# Gimbal_Controller_Board.net
KiCad netlist of a schematic drawn in EAGLE
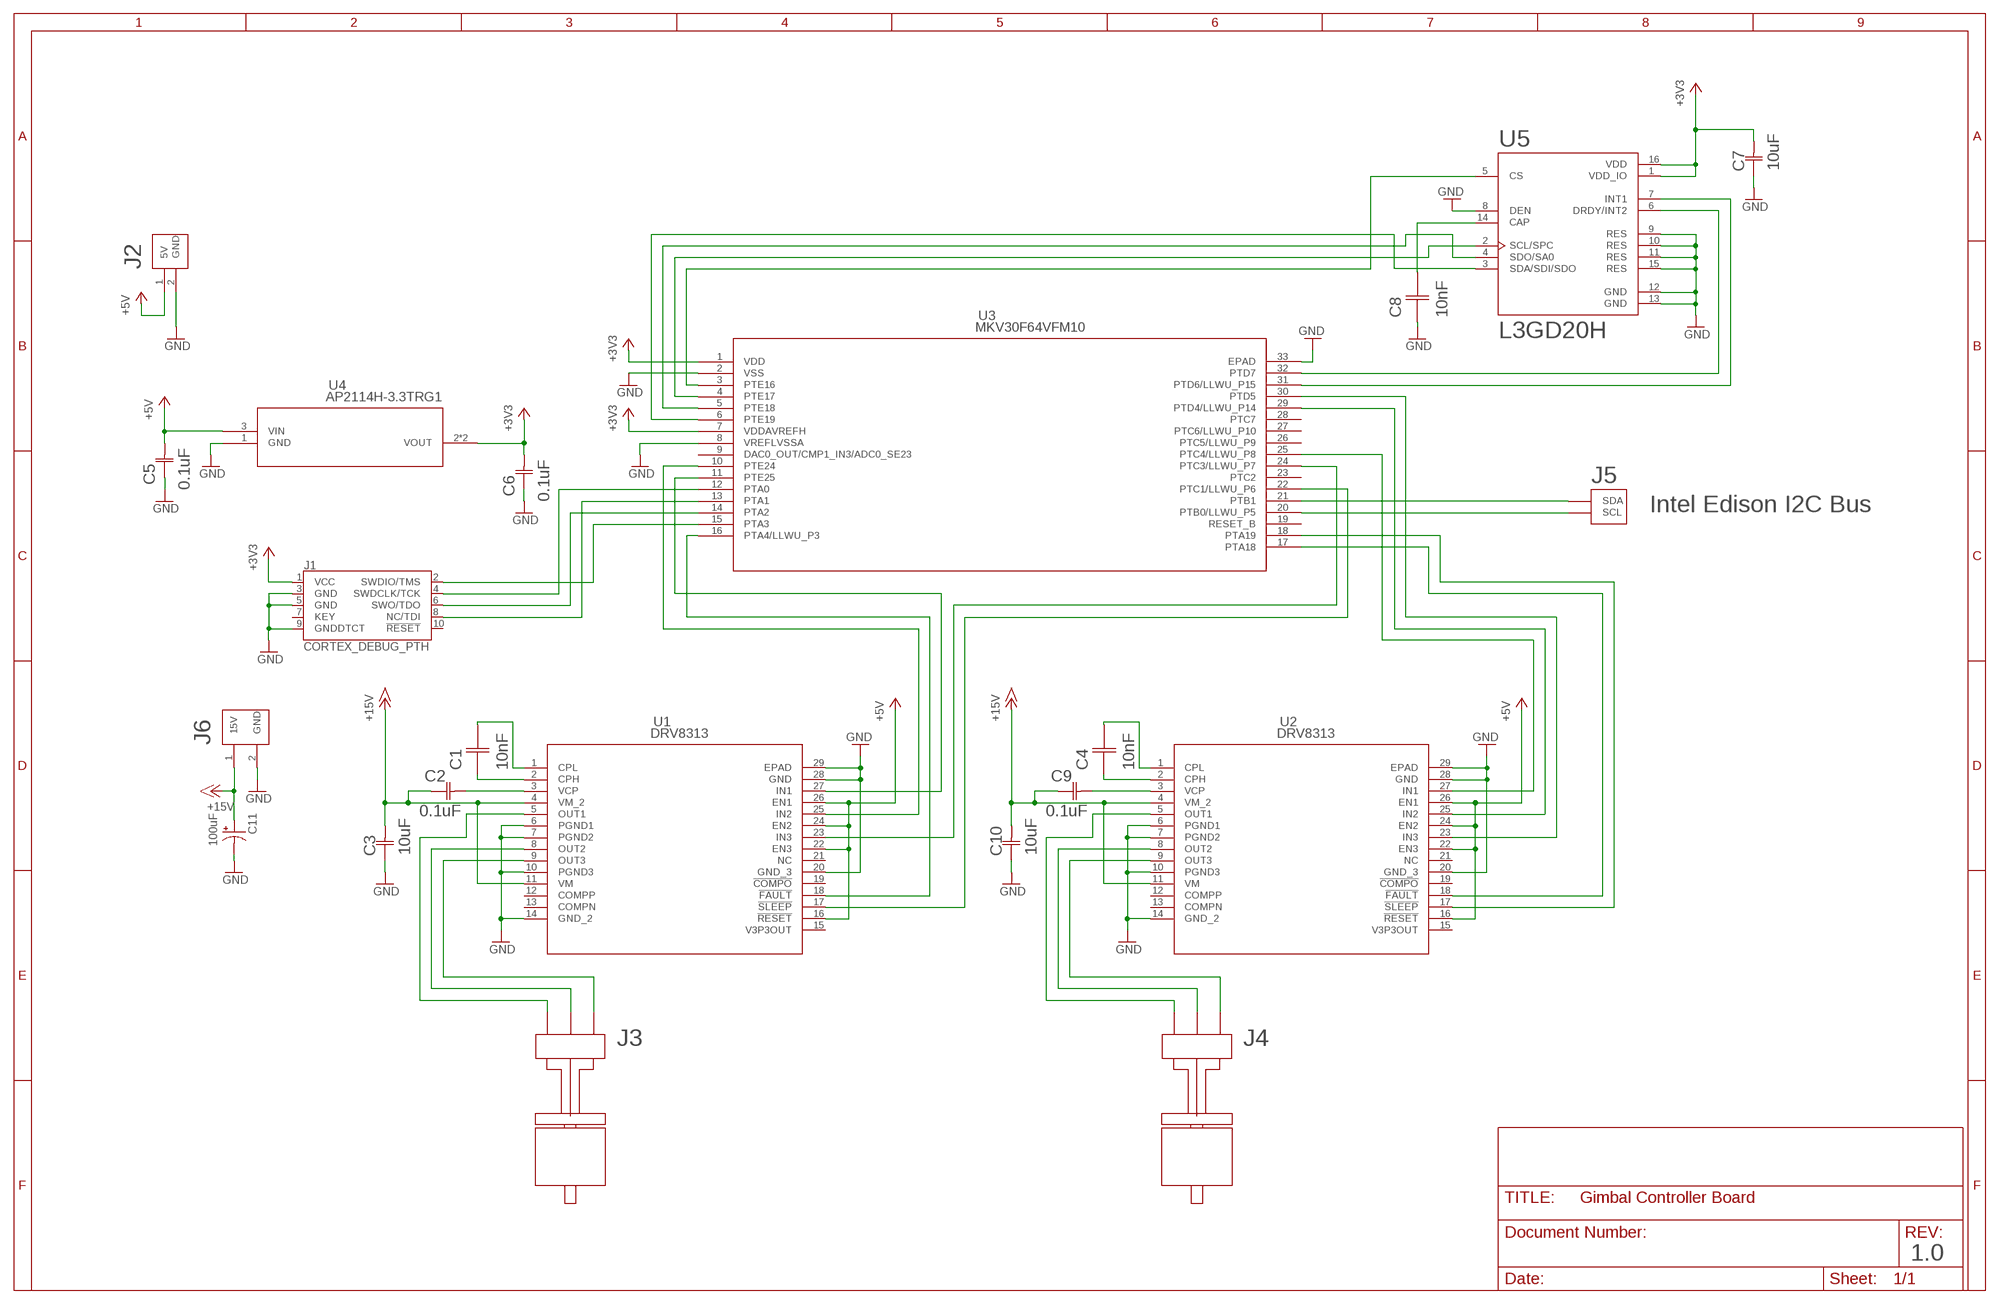
[diagram p0: schematic, sheet 1]

(export (version "E")
  (design (tool "Eeschema 10.0.6"))
  (components
    (comp (ref "C1")
      (value "10nF")
      (footprint "eagle-import:0603_CAPACITOR")
      (libsource (lib "eagle-import") (part "10NF_CAPACITOR"))
    )
    (comp (ref "C2")
      (value "0.1uF")
      (footprint "eagle-import:0805")
      (fields
        (field (name "MANUFACTURER_PART_NUMBER") "08055C104KAT2A")
        (field (name "COPYRIGHT") "Copyright C 2015 Accelerated Designs. All rights reserved")
      )
      (libsource (lib "eagle-import") (part "08055C104KAT2A"))
    )
    (comp (ref "C3")
      (value "10uF")
      (footprint "eagle-import:G-21")
      (fields
        (field (name "MANUFACTURER_PART_NUMBER") "GRM21BR60J106ME19L")
        (field (name "COPYRIGHT") "Copyright C 2015 Accelerated Designs. All rights reserved")
      )
      (libsource (lib "eagle-import") (part "GRM21BR60J106ME19L"))
    )
    (comp (ref "C4")
      (value "10nF")
      (footprint "eagle-import:0603_CAPACITOR")
      (libsource (lib "eagle-import") (part "10NF_CAPACITOR"))
    )
    (comp (ref "C5")
      (value "0.1uF")
      (footprint "eagle-import:0805")
      (fields
        (field (name "MANUFACTURER_PART_NUMBER") "08055C104KAT2A")
        (field (name "COPYRIGHT") "Copyright C 2015 Accelerated Designs. All rights reserved")
      )
      (libsource (lib "eagle-import") (part "08055C104KAT2A"))
    )
    (comp (ref "C6")
      (value "0.1uF")
      (footprint "eagle-import:0805")
      (fields
        (field (name "MANUFACTURER_PART_NUMBER") "08055C104KAT2A")
        (field (name "COPYRIGHT") "Copyright C 2015 Accelerated Designs. All rights reserved")
      )
      (libsource (lib "eagle-import") (part "08055C104KAT2A"))
    )
    (comp (ref "C7")
      (value "10uF")
      (footprint "eagle-import:G-21")
      (fields
        (field (name "MANUFACTURER_PART_NUMBER") "GRM21BR60J106ME19L")
        (field (name "COPYRIGHT") "Copyright C 2015 Accelerated Designs. All rights reserved")
      )
      (libsource (lib "eagle-import") (part "GRM21BR60J106ME19L"))
    )
    (comp (ref "C8")
      (value "10nF")
      (footprint "eagle-import:0603_CAPACITOR")
      (libsource (lib "eagle-import") (part "10NF_CAPACITOR"))
    )
    (comp (ref "C9")
      (value "0.1uF")
      (footprint "eagle-import:0805")
      (fields
        (field (name "MANUFACTURER_PART_NUMBER") "08055C104KAT2A")
        (field (name "COPYRIGHT") "Copyright C 2015 Accelerated Designs. All rights reserved")
      )
      (libsource (lib "eagle-import") (part "08055C104KAT2A"))
    )
    (comp (ref "C10")
      (value "10uF")
      (footprint "eagle-import:G-21")
      (fields
        (field (name "MANUFACTURER_PART_NUMBER") "GRM21BR60J106ME19L")
        (field (name "COPYRIGHT") "Copyright C 2015 Accelerated Designs. All rights reserved")
      )
      (libsource (lib "eagle-import") (part "GRM21BR60J106ME19L"))
    )
    (comp (ref "C11")
      (value "100uF")
      (footprint "eagle-import:0810_POLCAP")
      (libsource (lib "eagle-import") (part "100UF_CAPACITOR"))
    )
    (comp (ref "J1")
      (value "CORTEX_DEBUG_PTH")
      (footprint "eagle-import:2X5-PTH-1.27MM")
      (libsource (lib "eagle-import") (part "CORTEX_DEBUG_PTH"))
    )
    (comp (ref "J2")
      (value "POWER_CONNECTOR")
      (footprint "eagle-import:XH_CONNECTOR")
      (libsource (lib "eagle-import") (part "POWER_CONNECTOR"))
    )
    (comp (ref "J3")
      (value "BLDC_MOTOR_CONNECTOR")
      (footprint "eagle-import:JST-XH_3POS")
      (libsource (lib "eagle-import") (part "BLDC_MOTOR_CONNECTOR"))
    )
    (comp (ref "J4")
      (value "BLDC_MOTOR_CONNECTOR")
      (footprint "eagle-import:JST-XH_3POS")
      (libsource (lib "eagle-import") (part "BLDC_MOTOR_CONNECTOR"))
    )
    (comp (ref "J5")
      (value "I2C_CONNECTOR")
      (footprint "eagle-import:XH_CONNECTOR")
      (libsource (lib "eagle-import") (part "I2C_CONNECTOR"))
    )
    (comp (ref "J6")
      (value "GIMBAL_POWER_CONNECTOR")
      (footprint "eagle-import:XH_CONNECTOR")
      (libsource (lib "eagle-import") (part "GIMBAL_POWER_CONNECTOR"))
    )
    (comp (ref "U1")
      (value "DRV8313")
      (footprint "eagle-import:PWP28_5P18X3P1-M")
      (fields (field (name "MANUFACTURER_PART_NUMBER") "drv8313pwp"))
      (libsource (lib "eagle-import") (part "DRV8313PWPRPWP28_5P18X3P1-M"))
    )
    (comp (ref "U2")
      (value "DRV8313")
      (footprint "eagle-import:PWP28_5P18X3P1-M")
      (fields (field (name "MANUFACTURER_PART_NUMBER") "drv8313pwp"))
      (libsource (lib "eagle-import") (part "DRV8313PWPRPWP28_5P18X3P1-M"))
    )
    (comp (ref "U3")
      (value "MKV30F64VFM10")
      (footprint "eagle-import:QFN-32_5X5X0.9")
      (fields (field (name "MANUFACTURER_PART_NUMBER") "mkv30f64vfm10"))
      (libsource (lib "eagle-import") (part "MKV30F64VFM10"))
    )
    (comp (ref "U4")
      (value "AP2114H-3.3TRG1")
      (footprint "eagle-import:SOT-223")
      (fields (field (name "MANUFACTURER_PART_NUMBER") "ap2114h3.3trg1"))
      (libsource (lib "eagle-import") (part "AP2114H-3.3TRG1"))
    )
    (comp (ref "U5")
      (value "L3GD20H")
      (footprint "eagle-import:LGA16R50P7X5_300X300X100")
      (fields (field (name "MF") "STMicroelectronics"))
      (libsource (lib "eagle-import") (part "L3GD20H"))
    )
  )
  (nets
    (net (code "1") (name "+3V3") (class "Default")
      (node (ref "C6") (pin "2") (pinfunction "2_2") (pintype "passive"))
      (node (ref "C7") (pin "2") (pinfunction "22_2") (pintype "passive"))
      (node (ref "J1") (pin "1") (pinfunction "VCC_1") (pintype "bidirectional"))
      (node (ref "U3") (pin "1") (pinfunction "VDD_1") (pintype "power_in"))
      (node (ref "U3") (pin "7") (pinfunction "VDDAVREFH_7") (pintype "power_in"))
      (node (ref "U4") (pin "2") (pinfunction "VOUT_2") (pintype "output"))
      (node (ref "U4") (pin "4") (pinfunction "VOUT_4") (pintype "output"))
      (node (ref "U5") (pin "1") (pinfunction "VDD_IO_1") (pintype "power_in"))
      (node (ref "U5") (pin "16") (pinfunction "VDD_16") (pintype "power_in"))
    )
    (net (code "2") (name "+5V") (class "Default")
      (node (ref "C5") (pin "2") (pinfunction "2_2") (pintype "passive"))
      (node (ref "J2") (pin "1") (pinfunction "5V_1") (pintype "power_in"))
      (node (ref "U1") (pin "16") (pinfunction "~{RESET}_16") (pintype "input"))
      (node (ref "U1") (pin "22") (pinfunction "EN3_22") (pintype "input"))
      (node (ref "U1") (pin "24") (pinfunction "EN2_24") (pintype "input"))
      (node (ref "U1") (pin "26") (pinfunction "EN1_26") (pintype "input"))
      (node (ref "U2") (pin "16") (pinfunction "~{RESET}_16") (pintype "input"))
      (node (ref "U2") (pin "22") (pinfunction "EN3_22") (pintype "input"))
      (node (ref "U2") (pin "24") (pinfunction "EN2_24") (pintype "input"))
      (node (ref "U2") (pin "26") (pinfunction "EN1_26") (pintype "input"))
      (node (ref "U4") (pin "3") (pinfunction "VIN_3") (pintype "input"))
    )
    (net (code "3") (name "+15V") (class "Default")
      (node (ref "C10") (pin "2") (pinfunction "22_2") (pintype "passive"))
      (node (ref "C11") (pin "+") (pinfunction "+_+") (pintype "passive"))
      (node (ref "C2") (pin "1") (pinfunction "1_1") (pintype "passive"))
      (node (ref "C3") (pin "2") (pinfunction "22_2") (pintype "passive"))
      (node (ref "C9") (pin "1") (pinfunction "1_1") (pintype "passive"))
      (node (ref "J6") (pin "1") (pinfunction "15V_1") (pintype "power_in"))
      (node (ref "U1") (pin "11") (pinfunction "VM_11") (pintype "power_in"))
      (node (ref "U1") (pin "4") (pinfunction "VM_2_4") (pintype "power_in"))
      (node (ref "U2") (pin "11") (pinfunction "VM_11") (pintype "power_in"))
      (node (ref "U2") (pin "4") (pinfunction "VM_2_4") (pintype "power_in"))
    )
    (net (code "4") (name "GND") (class "Default")
      (node (ref "C10") (pin "1") (pinfunction "11_1") (pintype "passive"))
      (node (ref "C11") (pin "-") (pinfunction "-_-") (pintype "passive"))
      (node (ref "C3") (pin "1") (pinfunction "11_1") (pintype "passive"))
      (node (ref "C5") (pin "1") (pinfunction "1_1") (pintype "passive"))
      (node (ref "C6") (pin "1") (pinfunction "1_1") (pintype "passive"))
      (node (ref "C7") (pin "1") (pinfunction "11_1") (pintype "passive"))
      (node (ref "C8") (pin "1") (pinfunction "1_1") (pintype "bidirectional"))
      (node (ref "J1") (pin "3") (pinfunction "GND_3") (pintype "bidirectional"))
      (node (ref "J1") (pin "5") (pinfunction "GND_5") (pintype "bidirectional"))
      (node (ref "J1") (pin "9") (pinfunction "GNDDTCT_9") (pintype "bidirectional"))
      (node (ref "J2") (pin "2") (pinfunction "GND_2") (pintype "power_in"))
      (node (ref "J6") (pin "2") (pinfunction "GND_2") (pintype "power_in"))
      (node (ref "U1") (pin "10") (pinfunction "PGND3_10") (pintype "power_in"))
      (node (ref "U1") (pin "14") (pinfunction "GND_2_14") (pintype "power_in"))
      (node (ref "U1") (pin "20") (pinfunction "GND_3_20") (pintype "power_in"))
      (node (ref "U1") (pin "28") (pinfunction "GND_28") (pintype "power_in"))
      (node (ref "U1") (pin "29") (pinfunction "EPAD_29") (pintype "passive"))
      (node (ref "U1") (pin "6") (pinfunction "PGND1_6") (pintype "power_in"))
      (node (ref "U1") (pin "7") (pinfunction "PGND2_7") (pintype "power_in"))
      (node (ref "U2") (pin "10") (pinfunction "PGND3_10") (pintype "power_in"))
      (node (ref "U2") (pin "14") (pinfunction "GND_2_14") (pintype "power_in"))
      (node (ref "U2") (pin "20") (pinfunction "GND_3_20") (pintype "power_in"))
      (node (ref "U2") (pin "28") (pinfunction "GND_28") (pintype "power_in"))
      (node (ref "U2") (pin "29") (pinfunction "EPAD_29") (pintype "passive"))
      (node (ref "U2") (pin "6") (pinfunction "PGND1_6") (pintype "power_in"))
      (node (ref "U2") (pin "7") (pinfunction "PGND2_7") (pintype "power_in"))
      (node (ref "U3") (pin "2") (pinfunction "VSS_2") (pintype "power_in"))
      (node (ref "U3") (pin "33") (pinfunction "EPAD_33") (pintype "passive"))
      (node (ref "U3") (pin "8") (pinfunction "VREFLVSSA_8") (pintype "power_in"))
      (node (ref "U4") (pin "1") (pinfunction "GND_1") (pintype "power_in"))
      (node (ref "U5") (pin "10") (pinfunction "RES_10") (pintype "power_in"))
      (node (ref "U5") (pin "11") (pinfunction "RES_11") (pintype "power_in"))
      (node (ref "U5") (pin "12") (pinfunction "GND_12") (pintype "power_in"))
      (node (ref "U5") (pin "13") (pinfunction "GND_13") (pintype "power_in"))
      (node (ref "U5") (pin "15") (pinfunction "RES_15") (pintype "power_in"))
      (node (ref "U5") (pin "8") (pinfunction "DEN_8") (pintype "input"))
      (node (ref "U5") (pin "9") (pinfunction "RES_9") (pintype "power_in"))
    )
    (net (code "5") (name "Net-(J1-NC{slash}TDI)") (class "Default")
      (node (ref "J1") (pin "8") (pinfunction "NC/TDI_8") (pintype "bidirectional"))
      (node (ref "U3") (pin "13") (pinfunction "PTA1_13") (pintype "bidirectional"))
    )
    (net (code "6") (name "Net-(J1-SWDCLK{slash}TCK)") (class "Default")
      (node (ref "J1") (pin "4") (pinfunction "SWDCLK/TCK_4") (pintype "bidirectional"))
      (node (ref "U3") (pin "12") (pinfunction "PTA0_12") (pintype "bidirectional"))
    )
    (net (code "7") (name "Net-(J1-SWDIO{slash}TMS)") (class "Default")
      (node (ref "J1") (pin "2") (pinfunction "SWDIO/TMS_2") (pintype "bidirectional"))
      (node (ref "U3") (pin "15") (pinfunction "PTA3_15") (pintype "bidirectional"))
    )
    (net (code "8") (name "Net-(J1-SWO{slash}TDO)") (class "Default")
      (node (ref "J1") (pin "6") (pinfunction "SWO/TDO_6") (pintype "bidirectional"))
      (node (ref "U3") (pin "14") (pinfunction "PTA2_14") (pintype "bidirectional"))
    )
    (net (code "9") (name "Net-(J3-1)") (class "Default")
      (node (ref "J3") (pin "P$1") (pinfunction "1_P$1") (pintype "power_in"))
      (node (ref "U1") (pin "5") (pinfunction "OUT1_5") (pintype "output"))
    )
    (net (code "10") (name "Net-(J3-2)") (class "Default")
      (node (ref "J3") (pin "P$2") (pinfunction "2_P$2") (pintype "power_in"))
      (node (ref "U1") (pin "8") (pinfunction "OUT2_8") (pintype "output"))
    )
    (net (code "11") (name "Net-(J3-3)") (class "Default")
      (node (ref "J3") (pin "P$3") (pinfunction "3_P$3") (pintype "power_in"))
      (node (ref "U1") (pin "9") (pinfunction "OUT3_9") (pintype "output"))
    )
    (net (code "12") (name "Net-(J4-1)") (class "Default")
      (node (ref "J4") (pin "P$1") (pinfunction "1_P$1") (pintype "power_in"))
      (node (ref "U2") (pin "5") (pinfunction "OUT1_5") (pintype "output"))
    )
    (net (code "13") (name "Net-(J4-2)") (class "Default")
      (node (ref "J4") (pin "P$2") (pinfunction "2_P$2") (pintype "power_in"))
      (node (ref "U2") (pin "8") (pinfunction "OUT2_8") (pintype "output"))
    )
    (net (code "14") (name "Net-(J4-3)") (class "Default")
      (node (ref "J4") (pin "P$3") (pinfunction "3_P$3") (pintype "power_in"))
      (node (ref "U2") (pin "9") (pinfunction "OUT3_9") (pintype "output"))
    )
    (net (code "15") (name "Net-(J5-SCL)") (class "Default")
      (node (ref "J5") (pin "1") (pinfunction "SCL_1") (pintype "bidirectional"))
      (node (ref "U3") (pin "20") (pinfunction "PTB0/LLWU_P5_20") (pintype "bidirectional"))
    )
    (net (code "16") (name "Net-(J5-SDA)") (class "Default")
      (node (ref "J5") (pin "2") (pinfunction "SDA_2") (pintype "bidirectional"))
      (node (ref "U3") (pin "21") (pinfunction "PTB1_21") (pintype "bidirectional"))
    )
    (net (code "17") (name "Net-(U1-CPH)") (class "Default")
      (node (ref "C1") (pin "1") (pinfunction "1_1") (pintype "bidirectional"))
      (node (ref "U1") (pin "2") (pinfunction "CPH_2") (pintype "bidirectional"))
    )
    (net (code "18") (name "Net-(U1-CPL)") (class "Default")
      (node (ref "C1") (pin "2") (pinfunction "2_2") (pintype "bidirectional"))
      (node (ref "U1") (pin "1") (pinfunction "CPL_1") (pintype "bidirectional"))
    )
    (net (code "19") (name "Net-(U1-IN1)") (class "Default")
      (node (ref "U1") (pin "27") (pinfunction "IN1_27") (pintype "input"))
      (node (ref "U3") (pin "11") (pinfunction "PTE25_11") (pintype "bidirectional"))
    )
    (net (code "20") (name "Net-(U1-IN2)") (class "Default")
      (node (ref "U1") (pin "25") (pinfunction "IN2_25") (pintype "input"))
      (node (ref "U3") (pin "10") (pinfunction "PTE24_10") (pintype "bidirectional"))
    )
    (net (code "21") (name "Net-(U1-IN3)") (class "Default")
      (node (ref "U1") (pin "23") (pinfunction "IN3_23") (pintype "input"))
      (node (ref "U3") (pin "24") (pinfunction "PTC3/LLWU_P7_24") (pintype "bidirectional"))
    )
    (net (code "22") (name "Net-(U1-VCP)") (class "Default")
      (node (ref "C2") (pin "2") (pinfunction "2_2") (pintype "passive"))
      (node (ref "U1") (pin "3") (pinfunction "VCP_3") (pintype "bidirectional"))
    )
    (net (code "23") (name "Net-(U1-~{FAULT})") (class "Default")
      (node (ref "U1") (pin "18") (pinfunction "~{FAULT}_18") (pintype "output"))
      (node (ref "U3") (pin "16") (pinfunction "PTA4/LLWU_P3_16") (pintype "bidirectional"))
    )
    (net (code "24") (name "Net-(U1-~{SLEEP})") (class "Default")
      (node (ref "U1") (pin "17") (pinfunction "~{SLEEP}_17") (pintype "input"))
      (node (ref "U3") (pin "22") (pinfunction "PTC1/LLWU_P6_22") (pintype "bidirectional"))
    )
    (net (code "25") (name "Net-(U2-CPH)") (class "Default")
      (node (ref "C4") (pin "1") (pinfunction "1_1") (pintype "bidirectional"))
      (node (ref "U2") (pin "2") (pinfunction "CPH_2") (pintype "bidirectional"))
    )
    (net (code "26") (name "Net-(U2-CPL)") (class "Default")
      (node (ref "C4") (pin "2") (pinfunction "2_2") (pintype "bidirectional"))
      (node (ref "U2") (pin "1") (pinfunction "CPL_1") (pintype "bidirectional"))
    )
    (net (code "27") (name "Net-(U2-IN1)") (class "Default")
      (node (ref "U2") (pin "27") (pinfunction "IN1_27") (pintype "input"))
      (node (ref "U3") (pin "25") (pinfunction "PTC4/LLWU_P8_25") (pintype "bidirectional"))
    )
    (net (code "28") (name "Net-(U2-IN2)") (class "Default")
      (node (ref "U2") (pin "25") (pinfunction "IN2_25") (pintype "input"))
      (node (ref "U3") (pin "29") (pinfunction "PTD4/LLWU_P14_29") (pintype "bidirectional"))
    )
    (net (code "29") (name "Net-(U2-IN3)") (class "Default")
      (node (ref "U2") (pin "23") (pinfunction "IN3_23") (pintype "input"))
      (node (ref "U3") (pin "30") (pinfunction "PTD5_30") (pintype "bidirectional"))
    )
    (net (code "30") (name "Net-(U2-VCP)") (class "Default")
      (node (ref "C9") (pin "2") (pinfunction "2_2") (pintype "passive"))
      (node (ref "U2") (pin "3") (pinfunction "VCP_3") (pintype "bidirectional"))
    )
    (net (code "31") (name "Net-(U2-~{FAULT})") (class "Default")
      (node (ref "U2") (pin "18") (pinfunction "~{FAULT}_18") (pintype "output"))
      (node (ref "U3") (pin "17") (pinfunction "PTA18_17") (pintype "bidirectional"))
    )
    (net (code "32") (name "Net-(U2-~{SLEEP})") (class "Default")
      (node (ref "U2") (pin "17") (pinfunction "~{SLEEP}_17") (pintype "input"))
      (node (ref "U3") (pin "18") (pinfunction "PTA19_18") (pintype "bidirectional"))
    )
    (net (code "33") (name "Net-(U3-PTD6{slash}LLWU_P15)") (class "Default")
      (node (ref "U3") (pin "31") (pinfunction "PTD6/LLWU_P15_31") (pintype "bidirectional"))
      (node (ref "U5") (pin "7") (pinfunction "INT1_7") (pintype "output"))
    )
    (net (code "34") (name "Net-(U3-PTD7)") (class "Default")
      (node (ref "U3") (pin "32") (pinfunction "PTD7_32") (pintype "bidirectional"))
      (node (ref "U5") (pin "6") (pinfunction "DRDY/INT2_6") (pintype "output"))
    )
    (net (code "35") (name "Net-(U3-PTE16)") (class "Default")
      (node (ref "U3") (pin "3") (pinfunction "PTE16_3") (pintype "bidirectional"))
      (node (ref "U5") (pin "5") (pinfunction "CS_5") (pintype "input"))
    )
    (net (code "36") (name "Net-(U3-PTE17)") (class "Default")
      (node (ref "U3") (pin "4") (pinfunction "PTE17_4") (pintype "bidirectional"))
      (node (ref "U5") (pin "2") (pinfunction "SCL/SPC_2") (pintype "input"))
    )
    (net (code "37") (name "Net-(U3-PTE18)") (class "Default")
      (node (ref "U3") (pin "5") (pinfunction "PTE18_5") (pintype "bidirectional"))
      (node (ref "U5") (pin "4") (pinfunction "SDO/SA0_4") (pintype "bidirectional"))
    )
    (net (code "38") (name "Net-(U3-PTE19)") (class "Default")
      (node (ref "U3") (pin "6") (pinfunction "PTE19_6") (pintype "bidirectional"))
      (node (ref "U5") (pin "3") (pinfunction "SDA/SDI/SDO_3") (pintype "bidirectional"))
    )
    (net (code "39") (name "Net-(U5-CAP)") (class "Default")
      (node (ref "C8") (pin "2") (pinfunction "2_2") (pintype "bidirectional"))
      (node (ref "U5") (pin "14") (pinfunction "CAP_14") (pintype "passive"))
    )
    (net (code "40") (name "unconnected-(J1-KEY-Pad7)") (class "Default")
      (node (ref "J1") (pin "7") (pinfunction "KEY_7") (pintype "bidirectional"))
    )
    (net (code "41") (name "unconnected-(J1-~{RESET}-Pad10)") (class "Default")
      (node (ref "J1") (pin "10") (pinfunction "~{RESET}_10") (pintype "bidirectional"))
    )
    (net (code "42") (name "unconnected-(U1-COMPN-Pad13)") (class "Default")
      (node (ref "U1") (pin "13") (pinfunction "COMPN_13") (pintype "input"))
    )
    (net (code "43") (name "unconnected-(U1-COMPP-Pad12)") (class "Default")
      (node (ref "U1") (pin "12") (pinfunction "COMPP_12") (pintype "input"))
    )
    (net (code "44") (name "unconnected-(U1-NC-Pad21)") (class "Default")
      (node (ref "U1") (pin "21") (pinfunction "NC_21") (pintype "no_connect"))
    )
    (net (code "45") (name "unconnected-(U1-V3P3OUT-Pad15)") (class "Default")
      (node (ref "U1") (pin "15") (pinfunction "V3P3OUT_15") (pintype "output"))
    )
    (net (code "46") (name "unconnected-(U1-~{COMPO}-Pad19)") (class "Default")
      (node (ref "U1") (pin "19") (pinfunction "~{COMPO}_19") (pintype "output"))
    )
    (net (code "47") (name "unconnected-(U2-COMPN-Pad13)") (class "Default")
      (node (ref "U2") (pin "13") (pinfunction "COMPN_13") (pintype "input"))
    )
    (net (code "48") (name "unconnected-(U2-COMPP-Pad12)") (class "Default")
      (node (ref "U2") (pin "12") (pinfunction "COMPP_12") (pintype "input"))
    )
    (net (code "49") (name "unconnected-(U2-NC-Pad21)") (class "Default")
      (node (ref "U2") (pin "21") (pinfunction "NC_21") (pintype "no_connect"))
    )
    (net (code "50") (name "unconnected-(U2-V3P3OUT-Pad15)") (class "Default")
      (node (ref "U2") (pin "15") (pinfunction "V3P3OUT_15") (pintype "output"))
    )
    (net (code "51") (name "unconnected-(U2-~{COMPO}-Pad19)") (class "Default")
      (node (ref "U2") (pin "19") (pinfunction "~{COMPO}_19") (pintype "output"))
    )
    (net (code "52") (name "unconnected-(U3-DAC0_OUT{slash}CMP1_IN3{slash}ADC0_SE23-Pad9)") (class "Default")
      (node (ref "U3") (pin "9") (pinfunction "DAC0_OUT/CMP1_IN3/ADC0_SE23_9") (pintype "bidirectional"))
    )
    (net (code "53") (name "unconnected-(U3-PTC2-Pad23)") (class "Default")
      (node (ref "U3") (pin "23") (pinfunction "PTC2_23") (pintype "bidirectional"))
    )
    (net (code "54") (name "unconnected-(U3-PTC5{slash}LLWU_P9-Pad26)") (class "Default")
      (node (ref "U3") (pin "26") (pinfunction "PTC5/LLWU_P9_26") (pintype "bidirectional"))
    )
    (net (code "55") (name "unconnected-(U3-PTC6{slash}LLWU_P10-Pad27)") (class "Default")
      (node (ref "U3") (pin "27") (pinfunction "PTC6/LLWU_P10_27") (pintype "bidirectional"))
    )
    (net (code "56") (name "unconnected-(U3-PTC7-Pad28)") (class "Default")
      (node (ref "U3") (pin "28") (pinfunction "PTC7_28") (pintype "bidirectional"))
    )
    (net (code "57") (name "unconnected-(U3-RESET_B-Pad19)") (class "Default")
      (node (ref "U3") (pin "19") (pinfunction "RESET_B_19") (pintype "passive"))
    )
  )
)
